# keyboardAV.net
KiCad netlist of a schematic drawn in EAGLE
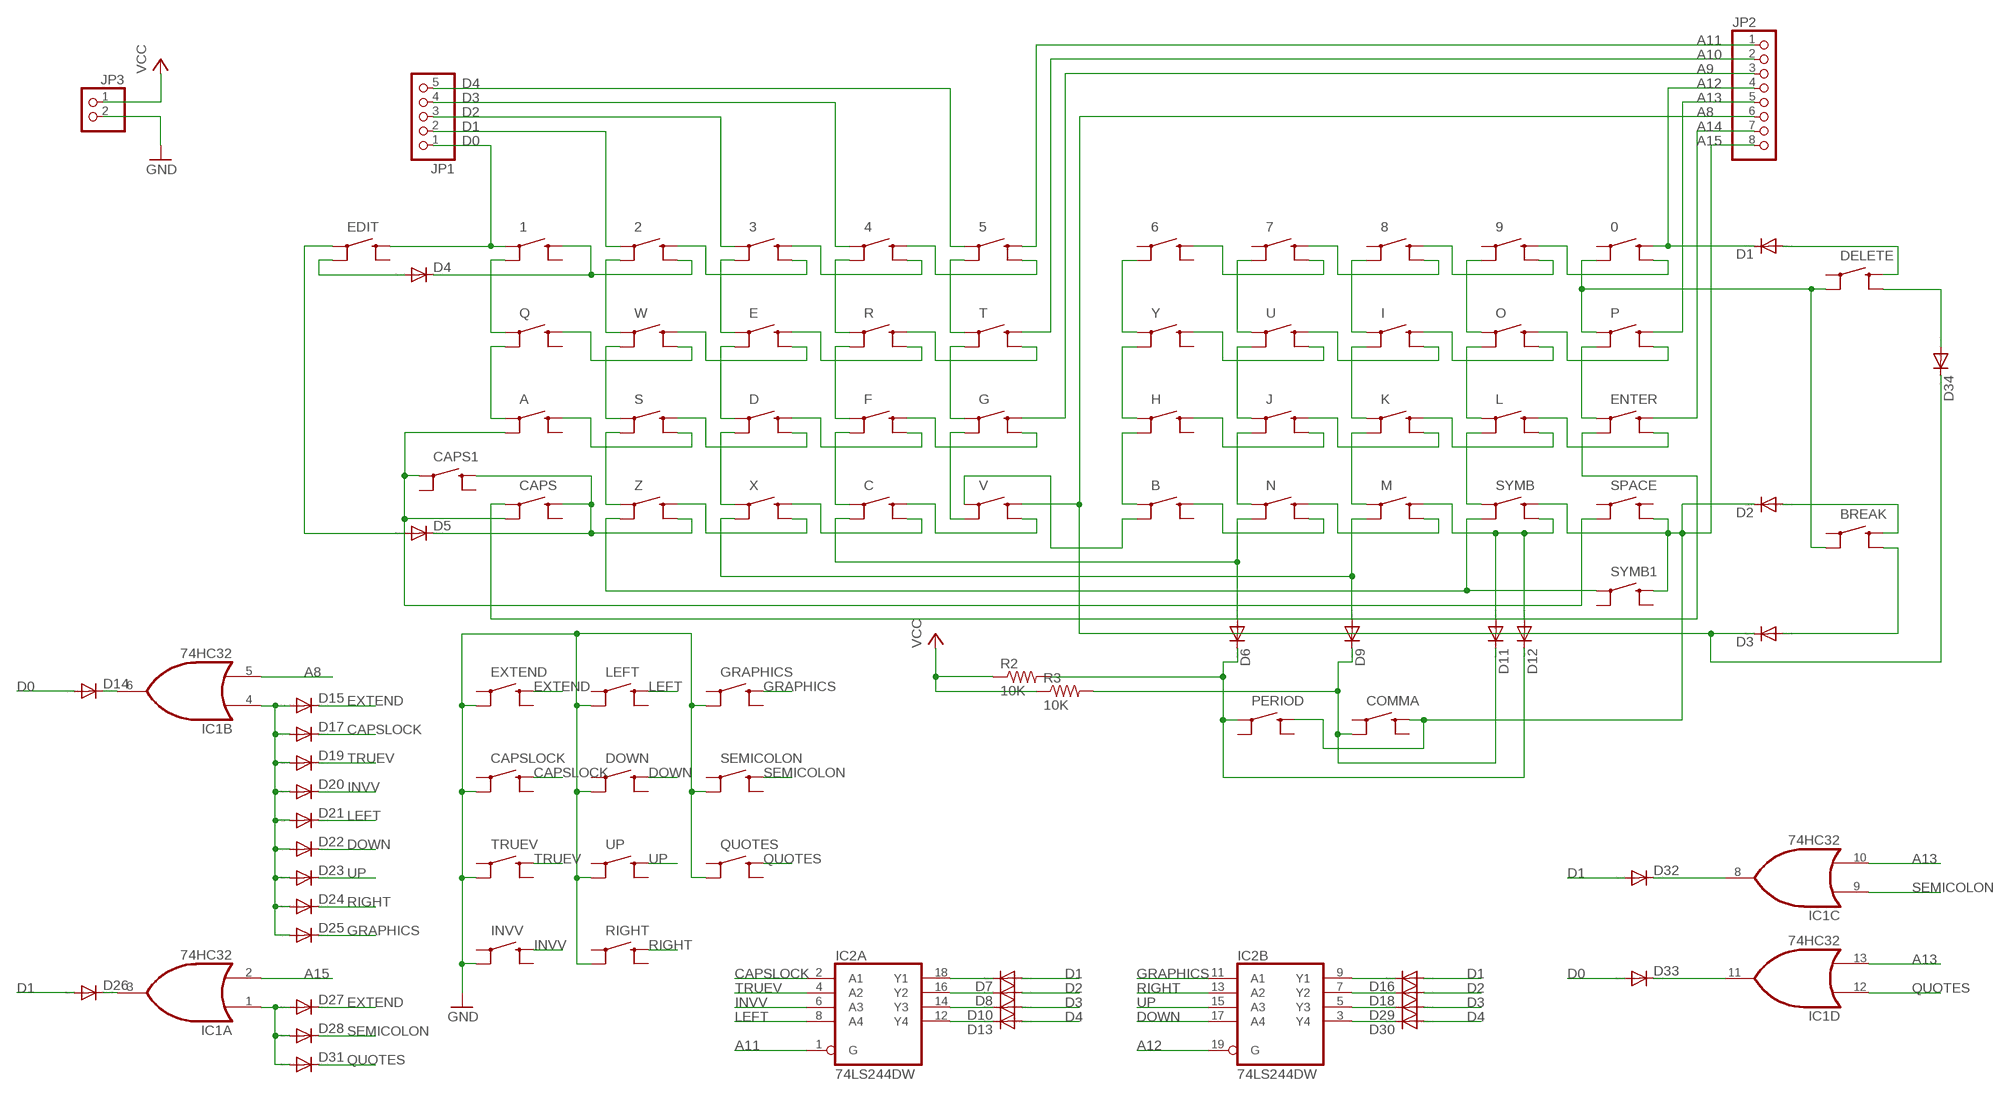
[diagram p0: schematic, sheet 1]

(export (version "E")
  (design (tool "Eeschema 10.0.6"))
  (components
    (comp (ref "0")
      (value "SWITCH-MOMENTARY-2SMD")
      (footprint "eagle-import:TACTILE-SWITCH-SMD")
      (libsource (lib "eagle-import") (part "SWITCH-MOMENTARY-2SMD"))
    )
    (comp (ref "1")
      (value "SWITCH-MOMENTARY-2SMD")
      (footprint "eagle-import:TACTILE-SWITCH-SMD")
      (libsource (lib "eagle-import") (part "SWITCH-MOMENTARY-2SMD"))
    )
    (comp (ref "2")
      (value "SWITCH-MOMENTARY-2SMD")
      (footprint "eagle-import:TACTILE-SWITCH-SMD")
      (libsource (lib "eagle-import") (part "SWITCH-MOMENTARY-2SMD"))
    )
    (comp (ref "3")
      (value "SWITCH-MOMENTARY-2SMD")
      (footprint "eagle-import:TACTILE-SWITCH-SMD")
      (libsource (lib "eagle-import") (part "SWITCH-MOMENTARY-2SMD"))
    )
    (comp (ref "4")
      (value "SWITCH-MOMENTARY-2SMD")
      (footprint "eagle-import:TACTILE-SWITCH-SMD")
      (libsource (lib "eagle-import") (part "SWITCH-MOMENTARY-2SMD"))
    )
    (comp (ref "5")
      (value "SWITCH-MOMENTARY-2SMD")
      (footprint "eagle-import:TACTILE-SWITCH-SMD")
      (libsource (lib "eagle-import") (part "SWITCH-MOMENTARY-2SMD"))
    )
    (comp (ref "6")
      (value "SWITCH-MOMENTARY-2SMD")
      (footprint "eagle-import:TACTILE-SWITCH-SMD")
      (libsource (lib "eagle-import") (part "SWITCH-MOMENTARY-2SMD"))
    )
    (comp (ref "7")
      (value "SWITCH-MOMENTARY-2SMD")
      (footprint "eagle-import:TACTILE-SWITCH-SMD")
      (libsource (lib "eagle-import") (part "SWITCH-MOMENTARY-2SMD"))
    )
    (comp (ref "8")
      (value "SWITCH-MOMENTARY-2SMD")
      (footprint "eagle-import:TACTILE-SWITCH-SMD")
      (libsource (lib "eagle-import") (part "SWITCH-MOMENTARY-2SMD"))
    )
    (comp (ref "9")
      (value "SWITCH-MOMENTARY-2SMD")
      (footprint "eagle-import:TACTILE-SWITCH-SMD")
      (libsource (lib "eagle-import") (part "SWITCH-MOMENTARY-2SMD"))
    )
    (comp (ref "A")
      (value "SWITCH-MOMENTARY-2SMD")
      (footprint "eagle-import:TACTILE-SWITCH-SMD")
      (libsource (lib "eagle-import") (part "SWITCH-MOMENTARY-2SMD"))
    )
    (comp (ref "B")
      (value "SWITCH-MOMENTARY-2SMD")
      (footprint "eagle-import:TACTILE-SWITCH-SMD")
      (libsource (lib "eagle-import") (part "SWITCH-MOMENTARY-2SMD"))
    )
    (comp (ref "BREAK")
      (value "SWITCH-MOMENTARY-2SMD")
      (footprint "eagle-import:TACTILE-SWITCH-SMD")
      (libsource (lib "eagle-import") (part "SWITCH-MOMENTARY-2SMD"))
    )
    (comp (ref "C")
      (value "SWITCH-MOMENTARY-2SMD")
      (footprint "eagle-import:TACTILE-SWITCH-SMD")
      (libsource (lib "eagle-import") (part "SWITCH-MOMENTARY-2SMD"))
    )
    (comp (ref "CAPS")
      (value "SWITCH-MOMENTARY-2SMD")
      (footprint "eagle-import:TACTILE-SWITCH-SMD")
      (libsource (lib "eagle-import") (part "SWITCH-MOMENTARY-2SMD"))
    )
    (comp (ref "CAPS1")
      (value "SWITCH-MOMENTARY-2SMD")
      (footprint "eagle-import:TACTILE-SWITCH-SMD")
      (libsource (lib "eagle-import") (part "SWITCH-MOMENTARY-2SMD"))
    )
    (comp (ref "CAPSLOCK")
      (value "SWITCH-MOMENTARY-2SMD")
      (footprint "eagle-import:TACTILE-SWITCH-SMD")
      (libsource (lib "eagle-import") (part "SWITCH-MOMENTARY-2SMD"))
    )
    (comp (ref "COMMA")
      (value "SWITCH-MOMENTARY-2SMD")
      (footprint "eagle-import:TACTILE-SWITCH-SMD")
      (libsource (lib "eagle-import") (part "SWITCH-MOMENTARY-2SMD"))
    )
    (comp (ref "D")
      (value "SWITCH-MOMENTARY-2SMD")
      (footprint "eagle-import:TACTILE-SWITCH-SMD")
      (libsource (lib "eagle-import") (part "SWITCH-MOMENTARY-2SMD"))
    )
    (comp (ref "D1")
      (value "DIODE-SOD323-R")
      (footprint "eagle-import:SOD323-R")
      (libsource (lib "eagle-import") (part "DIODE-SOD323-R"))
    )
    (comp (ref "D2")
      (value "DIODE-SOD323-R")
      (footprint "eagle-import:SOD323-R")
      (libsource (lib "eagle-import") (part "DIODE-SOD323-R"))
    )
    (comp (ref "D3")
      (value "DIODE-SOD323-R")
      (footprint "eagle-import:SOD323-R")
      (libsource (lib "eagle-import") (part "DIODE-SOD323-R"))
    )
    (comp (ref "D4")
      (value "DIODE-SOD323-R")
      (footprint "eagle-import:SOD323-R")
      (libsource (lib "eagle-import") (part "DIODE-SOD323-R"))
    )
    (comp (ref "D5")
      (value "DIODE-SOD323-R")
      (footprint "eagle-import:SOD323-R")
      (libsource (lib "eagle-import") (part "DIODE-SOD323-R"))
    )
    (comp (ref "D6")
      (value "DIODE-SOD323-R")
      (footprint "eagle-import:SOD323-R")
      (libsource (lib "eagle-import") (part "DIODE-SOD323-R"))
    )
    (comp (ref "D7")
      (value "DIODE-SOD323-R")
      (footprint "eagle-import:SOD323-R")
      (libsource (lib "eagle-import") (part "DIODE-SOD323-R"))
    )
    (comp (ref "D8")
      (value "DIODE-SOD323-R")
      (footprint "eagle-import:SOD323-R")
      (libsource (lib "eagle-import") (part "DIODE-SOD323-R"))
    )
    (comp (ref "D9")
      (value "DIODE-SOD323-R")
      (footprint "eagle-import:SOD323-R")
      (libsource (lib "eagle-import") (part "DIODE-SOD323-R"))
    )
    (comp (ref "D10")
      (value "DIODE-SOD323-R")
      (footprint "eagle-import:SOD323-R")
      (libsource (lib "eagle-import") (part "DIODE-SOD323-R"))
    )
    (comp (ref "D11")
      (value "DIODE-SOD323-R")
      (footprint "eagle-import:SOD323-R")
      (libsource (lib "eagle-import") (part "DIODE-SOD323-R"))
    )
    (comp (ref "D12")
      (value "DIODE-SOD323-R")
      (footprint "eagle-import:SOD323-R")
      (libsource (lib "eagle-import") (part "DIODE-SOD323-R"))
    )
    (comp (ref "D13")
      (value "DIODE-SOD323-R")
      (footprint "eagle-import:SOD323-R")
      (libsource (lib "eagle-import") (part "DIODE-SOD323-R"))
    )
    (comp (ref "D14")
      (value "DIODE-SOD323-R")
      (footprint "eagle-import:SOD323-R")
      (libsource (lib "eagle-import") (part "DIODE-SOD323-R"))
    )
    (comp (ref "D15")
      (value "DIODE-SOD323-R")
      (footprint "eagle-import:SOD323-R")
      (libsource (lib "eagle-import") (part "DIODE-SOD323-R"))
    )
    (comp (ref "D16")
      (value "DIODE-SOD323-R")
      (footprint "eagle-import:SOD323-R")
      (libsource (lib "eagle-import") (part "DIODE-SOD323-R"))
    )
    (comp (ref "D17")
      (value "DIODE-SOD323-R")
      (footprint "eagle-import:SOD323-R")
      (libsource (lib "eagle-import") (part "DIODE-SOD323-R"))
    )
    (comp (ref "D18")
      (value "DIODE-SOD323-R")
      (footprint "eagle-import:SOD323-R")
      (libsource (lib "eagle-import") (part "DIODE-SOD323-R"))
    )
    (comp (ref "D19")
      (value "DIODE-SOD323-R")
      (footprint "eagle-import:SOD323-R")
      (libsource (lib "eagle-import") (part "DIODE-SOD323-R"))
    )
    (comp (ref "D20")
      (value "DIODE-SOD323-R")
      (footprint "eagle-import:SOD323-R")
      (libsource (lib "eagle-import") (part "DIODE-SOD323-R"))
    )
    (comp (ref "D21")
      (value "DIODE-SOD323-R")
      (footprint "eagle-import:SOD323-R")
      (libsource (lib "eagle-import") (part "DIODE-SOD323-R"))
    )
    (comp (ref "D22")
      (value "DIODE-SOD323-R")
      (footprint "eagle-import:SOD323-R")
      (libsource (lib "eagle-import") (part "DIODE-SOD323-R"))
    )
    (comp (ref "D23")
      (value "DIODE-SOD323-R")
      (footprint "eagle-import:SOD323-R")
      (libsource (lib "eagle-import") (part "DIODE-SOD323-R"))
    )
    (comp (ref "D24")
      (value "DIODE-SOD323-R")
      (footprint "eagle-import:SOD323-R")
      (libsource (lib "eagle-import") (part "DIODE-SOD323-R"))
    )
    (comp (ref "D25")
      (value "DIODE-SOD323-R")
      (footprint "eagle-import:SOD323-R")
      (libsource (lib "eagle-import") (part "DIODE-SOD323-R"))
    )
    (comp (ref "D26")
      (value "DIODE-SOD323-R")
      (footprint "eagle-import:SOD323-R")
      (libsource (lib "eagle-import") (part "DIODE-SOD323-R"))
    )
    (comp (ref "D27")
      (value "DIODE-SOD323-R")
      (footprint "eagle-import:SOD323-R")
      (libsource (lib "eagle-import") (part "DIODE-SOD323-R"))
    )
    (comp (ref "D28")
      (value "DIODE-SOD323-R")
      (footprint "eagle-import:SOD323-R")
      (libsource (lib "eagle-import") (part "DIODE-SOD323-R"))
    )
    (comp (ref "D29")
      (value "DIODE-SOD323-R")
      (footprint "eagle-import:SOD323-R")
      (libsource (lib "eagle-import") (part "DIODE-SOD323-R"))
    )
    (comp (ref "D30")
      (value "DIODE-SOD323-R")
      (footprint "eagle-import:SOD323-R")
      (libsource (lib "eagle-import") (part "DIODE-SOD323-R"))
    )
    (comp (ref "D31")
      (value "DIODE-SOD323-R")
      (footprint "eagle-import:SOD323-R")
      (libsource (lib "eagle-import") (part "DIODE-SOD323-R"))
    )
    (comp (ref "D32")
      (value "DIODE-SOD323-R")
      (footprint "eagle-import:SOD323-R")
      (libsource (lib "eagle-import") (part "DIODE-SOD323-R"))
    )
    (comp (ref "D33")
      (value "DIODE-SOD323-R")
      (footprint "eagle-import:SOD323-R")
      (libsource (lib "eagle-import") (part "DIODE-SOD323-R"))
    )
    (comp (ref "D34")
      (value "DIODE-SOD323-R")
      (footprint "eagle-import:SOD323-R")
      (libsource (lib "eagle-import") (part "DIODE-SOD323-R"))
    )
    (comp (ref "DELETE")
      (value "SWITCH-MOMENTARY-2SMD")
      (footprint "eagle-import:TACTILE-SWITCH-SMD")
      (libsource (lib "eagle-import") (part "SWITCH-MOMENTARY-2SMD"))
    )
    (comp (ref "DOWN")
      (value "SWITCH-MOMENTARY-2SMD")
      (footprint "eagle-import:TACTILE-SWITCH-SMD")
      (libsource (lib "eagle-import") (part "SWITCH-MOMENTARY-2SMD"))
    )
    (comp (ref "E")
      (value "SWITCH-MOMENTARY-2SMD")
      (footprint "eagle-import:TACTILE-SWITCH-SMD")
      (libsource (lib "eagle-import") (part "SWITCH-MOMENTARY-2SMD"))
    )
    (comp (ref "EDIT")
      (value "SWITCH-MOMENTARY-2SMD")
      (footprint "eagle-import:TACTILE-SWITCH-SMD")
      (libsource (lib "eagle-import") (part "SWITCH-MOMENTARY-2SMD"))
    )
    (comp (ref "ENTER")
      (value "SWITCH-MOMENTARY-2SMD")
      (footprint "eagle-import:TACTILE-SWITCH-SMD")
      (libsource (lib "eagle-import") (part "SWITCH-MOMENTARY-2SMD"))
    )
    (comp (ref "EXTEND")
      (value "SWITCH-MOMENTARY-2SMD")
      (footprint "eagle-import:TACTILE-SWITCH-SMD")
      (libsource (lib "eagle-import") (part "SWITCH-MOMENTARY-2SMD"))
    )
    (comp (ref "F")
      (value "SWITCH-MOMENTARY-2SMD")
      (footprint "eagle-import:TACTILE-SWITCH-SMD")
      (libsource (lib "eagle-import") (part "SWITCH-MOMENTARY-2SMD"))
    )
    (comp (ref "G")
      (value "SWITCH-MOMENTARY-2SMD")
      (footprint "eagle-import:TACTILE-SWITCH-SMD")
      (libsource (lib "eagle-import") (part "SWITCH-MOMENTARY-2SMD"))
    )
    (comp (ref "GRAPHICS")
      (value "SWITCH-MOMENTARY-2SMD")
      (footprint "eagle-import:TACTILE-SWITCH-SMD")
      (libsource (lib "eagle-import") (part "SWITCH-MOMENTARY-2SMD"))
    )
    (comp (ref "H")
      (value "SWITCH-MOMENTARY-2SMD")
      (footprint "eagle-import:TACTILE-SWITCH-SMD")
      (libsource (lib "eagle-import") (part "SWITCH-MOMENTARY-2SMD"))
    )
    (comp (ref "I")
      (value "SWITCH-MOMENTARY-2SMD")
      (footprint "eagle-import:TACTILE-SWITCH-SMD")
      (libsource (lib "eagle-import") (part "SWITCH-MOMENTARY-2SMD"))
    )
    (comp (ref "IC1")
      (value "74HC32")
      (footprint "eagle-import:SO14")
      (libsource (lib "eagle-import") (part "7432DS"))
    )
    (comp (ref "IC2")
      (value "74LS244DW")
      (footprint "eagle-import:SO20W")
      (libsource (lib "eagle-import") (part "74244DWLS"))
    )
    (comp (ref "INVV")
      (value "SWITCH-MOMENTARY-2SMD")
      (footprint "eagle-import:TACTILE-SWITCH-SMD")
      (libsource (lib "eagle-import") (part "SWITCH-MOMENTARY-2SMD"))
    )
    (comp (ref "J")
      (value "SWITCH-MOMENTARY-2SMD")
      (footprint "eagle-import:TACTILE-SWITCH-SMD")
      (libsource (lib "eagle-import") (part "SWITCH-MOMENTARY-2SMD"))
    )
    (comp (ref "JP1")
      (value "PINHD-1X5")
      (footprint "eagle-import:1X05")
      (libsource (lib "eagle-import") (part "PINHD-1X5"))
    )
    (comp (ref "JP2")
      (value "PINHD-1X8")
      (footprint "eagle-import:1X08")
      (libsource (lib "eagle-import") (part "PINHD-1X8"))
    )
    (comp (ref "JP3")
      (value "PINHD-1X2")
      (footprint "eagle-import:1X02")
      (libsource (lib "eagle-import") (part "PINHD-1X2"))
    )
    (comp (ref "K")
      (value "SWITCH-MOMENTARY-2SMD")
      (footprint "eagle-import:TACTILE-SWITCH-SMD")
      (libsource (lib "eagle-import") (part "SWITCH-MOMENTARY-2SMD"))
    )
    (comp (ref "L")
      (value "SWITCH-MOMENTARY-2SMD")
      (footprint "eagle-import:TACTILE-SWITCH-SMD")
      (libsource (lib "eagle-import") (part "SWITCH-MOMENTARY-2SMD"))
    )
    (comp (ref "LEFT")
      (value "SWITCH-MOMENTARY-2SMD")
      (footprint "eagle-import:TACTILE-SWITCH-SMD")
      (libsource (lib "eagle-import") (part "SWITCH-MOMENTARY-2SMD"))
    )
    (comp (ref "M")
      (value "SWITCH-MOMENTARY-2SMD")
      (footprint "eagle-import:TACTILE-SWITCH-SMD")
      (libsource (lib "eagle-import") (part "SWITCH-MOMENTARY-2SMD"))
    )
    (comp (ref "N")
      (value "SWITCH-MOMENTARY-2SMD")
      (footprint "eagle-import:TACTILE-SWITCH-SMD")
      (libsource (lib "eagle-import") (part "SWITCH-MOMENTARY-2SMD"))
    )
    (comp (ref "O")
      (value "SWITCH-MOMENTARY-2SMD")
      (footprint "eagle-import:TACTILE-SWITCH-SMD")
      (libsource (lib "eagle-import") (part "SWITCH-MOMENTARY-2SMD"))
    )
    (comp (ref "P")
      (value "SWITCH-MOMENTARY-2SMD")
      (footprint "eagle-import:TACTILE-SWITCH-SMD")
      (libsource (lib "eagle-import") (part "SWITCH-MOMENTARY-2SMD"))
    )
    (comp (ref "PERIOD")
      (value "SWITCH-MOMENTARY-2SMD")
      (footprint "eagle-import:TACTILE-SWITCH-SMD")
      (libsource (lib "eagle-import") (part "SWITCH-MOMENTARY-2SMD"))
    )
    (comp (ref "Q")
      (value "SWITCH-MOMENTARY-2SMD")
      (footprint "eagle-import:TACTILE-SWITCH-SMD")
      (libsource (lib "eagle-import") (part "SWITCH-MOMENTARY-2SMD"))
    )
    (comp (ref "QUOTES")
      (value "SWITCH-MOMENTARY-2SMD")
      (footprint "eagle-import:TACTILE-SWITCH-SMD")
      (libsource (lib "eagle-import") (part "SWITCH-MOMENTARY-2SMD"))
    )
    (comp (ref "R")
      (value "SWITCH-MOMENTARY-2SMD")
      (footprint "eagle-import:TACTILE-SWITCH-SMD")
      (libsource (lib "eagle-import") (part "SWITCH-MOMENTARY-2SMD"))
    )
    (comp (ref "R2")
      (value "10K")
      (footprint "eagle-import:M0805")
      (libsource (lib "eagle-import") (part "R-US_M0805"))
    )
    (comp (ref "R3")
      (value "10K")
      (footprint "eagle-import:M0805")
      (libsource (lib "eagle-import") (part "R-US_M0805"))
    )
    (comp (ref "RIGHT")
      (value "SWITCH-MOMENTARY-2SMD")
      (footprint "eagle-import:TACTILE-SWITCH-SMD")
      (libsource (lib "eagle-import") (part "SWITCH-MOMENTARY-2SMD"))
    )
    (comp (ref "S")
      (value "SWITCH-MOMENTARY-2SMD")
      (footprint "eagle-import:TACTILE-SWITCH-SMD")
      (libsource (lib "eagle-import") (part "SWITCH-MOMENTARY-2SMD"))
    )
    (comp (ref "SEMICOLON")
      (value "SWITCH-MOMENTARY-2SMD")
      (footprint "eagle-import:TACTILE-SWITCH-SMD")
      (libsource (lib "eagle-import") (part "SWITCH-MOMENTARY-2SMD"))
    )
    (comp (ref "SPACE")
      (value "SWITCH-MOMENTARY-2SMD")
      (footprint "eagle-import:TACTILE-SWITCH-SMD")
      (libsource (lib "eagle-import") (part "SWITCH-MOMENTARY-2SMD"))
    )
    (comp (ref "SYMB")
      (value "SWITCH-MOMENTARY-2SMD")
      (footprint "eagle-import:TACTILE-SWITCH-SMD")
      (libsource (lib "eagle-import") (part "SWITCH-MOMENTARY-2SMD"))
    )
    (comp (ref "SYMB1")
      (value "SWITCH-MOMENTARY-2SMD")
      (footprint "eagle-import:TACTILE-SWITCH-SMD")
      (libsource (lib "eagle-import") (part "SWITCH-MOMENTARY-2SMD"))
    )
    (comp (ref "T")
      (value "SWITCH-MOMENTARY-2SMD")
      (footprint "eagle-import:TACTILE-SWITCH-SMD")
      (libsource (lib "eagle-import") (part "SWITCH-MOMENTARY-2SMD"))
    )
    (comp (ref "TRUEV")
      (value "SWITCH-MOMENTARY-2SMD")
      (footprint "eagle-import:TACTILE-SWITCH-SMD")
      (libsource (lib "eagle-import") (part "SWITCH-MOMENTARY-2SMD"))
    )
    (comp (ref "U")
      (value "SWITCH-MOMENTARY-2SMD")
      (footprint "eagle-import:TACTILE-SWITCH-SMD")
      (libsource (lib "eagle-import") (part "SWITCH-MOMENTARY-2SMD"))
    )
    (comp (ref "UP")
      (value "SWITCH-MOMENTARY-2SMD")
      (footprint "eagle-import:TACTILE-SWITCH-SMD")
      (libsource (lib "eagle-import") (part "SWITCH-MOMENTARY-2SMD"))
    )
    (comp (ref "V")
      (value "SWITCH-MOMENTARY-2SMD")
      (footprint "eagle-import:TACTILE-SWITCH-SMD")
      (libsource (lib "eagle-import") (part "SWITCH-MOMENTARY-2SMD"))
    )
    (comp (ref "W")
      (value "SWITCH-MOMENTARY-2SMD")
      (footprint "eagle-import:TACTILE-SWITCH-SMD")
      (libsource (lib "eagle-import") (part "SWITCH-MOMENTARY-2SMD"))
    )
    (comp (ref "X")
      (value "SWITCH-MOMENTARY-2SMD")
      (footprint "eagle-import:TACTILE-SWITCH-SMD")
      (libsource (lib "eagle-import") (part "SWITCH-MOMENTARY-2SMD"))
    )
    (comp (ref "Y")
      (value "SWITCH-MOMENTARY-2SMD")
      (footprint "eagle-import:TACTILE-SWITCH-SMD")
      (libsource (lib "eagle-import") (part "SWITCH-MOMENTARY-2SMD"))
    )
    (comp (ref "Z")
      (value "SWITCH-MOMENTARY-2SMD")
      (footprint "eagle-import:TACTILE-SWITCH-SMD")
      (libsource (lib "eagle-import") (part "SWITCH-MOMENTARY-2SMD"))
    )
  )
  (nets
    (net (code "1") (name "/A8") (class "Default")
      (node (ref "D3") (pin "C") (pinfunction "C_C") (pintype "passive"))
      (node (ref "D34") (pin "C") (pinfunction "C_C") (pintype "passive"))
      (node (ref "IC1") (pin "5") (pinfunction "I1_5") (pintype "input"))
      (node (ref "JP2") (pin "6") (pinfunction "6_6") (pintype "passive"))
      (node (ref "V") (pin "3") (pinfunction "2_3") (pintype "passive"))
    )
    (net (code "2") (name "/A9") (class "Default")
      (node (ref "G") (pin "3") (pinfunction "2_3") (pintype "passive"))
      (node (ref "JP2") (pin "3") (pinfunction "3_3") (pintype "passive"))
    )
    (net (code "3") (name "/A10") (class "Default")
      (node (ref "JP2") (pin "2") (pinfunction "2_2") (pintype "passive"))
      (node (ref "T") (pin "3") (pinfunction "2_3") (pintype "passive"))
    )
    (net (code "4") (name "/A11") (class "Default")
      (node (ref "5") (pin "3") (pinfunction "2_3") (pintype "passive"))
      (node (ref "IC2") (pin "1") (pinfunction "G_1") (pintype "input"))
      (node (ref "JP2") (pin "1") (pinfunction "1_1") (pintype "passive"))
    )
    (net (code "5") (name "/A12") (class "Default")
      (node (ref "0") (pin "3") (pinfunction "2_3") (pintype "passive"))
      (node (ref "D1") (pin "C") (pinfunction "C_C") (pintype "passive"))
      (node (ref "IC2") (pin "19") (pinfunction "G_19") (pintype "input"))
      (node (ref "JP2") (pin "4") (pinfunction "4_4") (pintype "passive"))
    )
    (net (code "6") (name "/A13") (class "Default")
      (node (ref "IC1") (pin "10") (pinfunction "I1_10") (pintype "input"))
      (node (ref "IC1") (pin "13") (pinfunction "I1_13") (pintype "input"))
      (node (ref "JP2") (pin "5") (pinfunction "5_5") (pintype "passive"))
      (node (ref "P") (pin "3") (pinfunction "2_3") (pintype "passive"))
    )
    (net (code "7") (name "/A14") (class "Default")
      (node (ref "ENTER") (pin "3") (pinfunction "2_3") (pintype "passive"))
      (node (ref "JP2") (pin "7") (pinfunction "7_7") (pintype "passive"))
    )
    (net (code "8") (name "/A15") (class "Default")
      (node (ref "COMMA") (pin "3") (pinfunction "2_3") (pintype "passive"))
      (node (ref "D2") (pin "C") (pinfunction "C_C") (pintype "passive"))
      (node (ref "IC1") (pin "2") (pinfunction "I1_2") (pintype "input"))
      (node (ref "JP2") (pin "8") (pinfunction "8_8") (pintype "passive"))
      (node (ref "PERIOD") (pin "3") (pinfunction "2_3") (pintype "passive"))
      (node (ref "SPACE") (pin "4") (pinfunction "4_4") (pintype "passive"))
      (node (ref "SYMB") (pin "3") (pinfunction "2_3") (pintype "passive"))
      (node (ref "SYMB1") (pin "3") (pinfunction "2_3") (pintype "passive"))
    )
    (net (code "9") (name "/CAPSLOCK") (class "Default")
      (node (ref "CAPSLOCK") (pin "3") (pinfunction "2_3") (pintype "passive"))
      (node (ref "D17") (pin "C") (pinfunction "C_C") (pintype "passive"))
      (node (ref "IC2") (pin "2") (pinfunction "A1_2") (pintype "input"))
    )
    (net (code "10") (name "/D0") (class "Default")
      (node (ref "1") (pin "1") (pinfunction "1_1") (pintype "passive"))
      (node (ref "D14") (pin "A") (pinfunction "A_A") (pintype "passive"))
      (node (ref "D33") (pin "A") (pinfunction "A_A") (pintype "passive"))
      (node (ref "EDIT") (pin "3") (pinfunction "2_3") (pintype "passive"))
      (node (ref "JP1") (pin "1") (pinfunction "1_1") (pintype "passive"))
    )
    (net (code "11") (name "/D1") (class "Default")
      (node (ref "2") (pin "1") (pinfunction "1_1") (pintype "passive"))
      (node (ref "D16") (pin "A") (pinfunction "A_A") (pintype "passive"))
      (node (ref "D26") (pin "A") (pinfunction "A_A") (pintype "passive"))
      (node (ref "D32") (pin "A") (pinfunction "A_A") (pintype "passive"))
      (node (ref "D7") (pin "A") (pinfunction "A_A") (pintype "passive"))
      (node (ref "JP1") (pin "2") (pinfunction "2_2") (pintype "passive"))
    )
    (net (code "12") (name "/D2") (class "Default")
      (node (ref "3") (pin "1") (pinfunction "1_1") (pintype "passive"))
      (node (ref "D18") (pin "A") (pinfunction "A_A") (pintype "passive"))
      (node (ref "D8") (pin "A") (pinfunction "A_A") (pintype "passive"))
      (node (ref "JP1") (pin "3") (pinfunction "3_3") (pintype "passive"))
    )
    (net (code "13") (name "/D3") (class "Default")
      (node (ref "4") (pin "1") (pinfunction "1_1") (pintype "passive"))
      (node (ref "D10") (pin "A") (pinfunction "A_A") (pintype "passive"))
      (node (ref "D29") (pin "A") (pinfunction "A_A") (pintype "passive"))
      (node (ref "JP1") (pin "4") (pinfunction "4_4") (pintype "passive"))
    )
    (net (code "14") (name "/D4") (class "Default")
      (node (ref "5") (pin "1") (pinfunction "1_1") (pintype "passive"))
      (node (ref "D13") (pin "A") (pinfunction "A_A") (pintype "passive"))
      (node (ref "D30") (pin "A") (pinfunction "A_A") (pintype "passive"))
      (node (ref "JP1") (pin "5") (pinfunction "5_5") (pintype "passive"))
    )
    (net (code "15") (name "/DOWN") (class "Default")
      (node (ref "D22") (pin "C") (pinfunction "C_C") (pintype "passive"))
      (node (ref "DOWN") (pin "3") (pinfunction "2_3") (pintype "passive"))
      (node (ref "IC2") (pin "17") (pinfunction "A4_17") (pintype "input"))
    )
    (net (code "16") (name "/EXTEND") (class "Default")
      (node (ref "D15") (pin "C") (pinfunction "C_C") (pintype "passive"))
      (node (ref "D27") (pin "C") (pinfunction "C_C") (pintype "passive"))
      (node (ref "EXTEND") (pin "3") (pinfunction "2_3") (pintype "passive"))
    )
    (net (code "17") (name "/GRAPHICS") (class "Default")
      (node (ref "D25") (pin "C") (pinfunction "C_C") (pintype "passive"))
      (node (ref "GRAPHICS") (pin "3") (pinfunction "2_3") (pintype "passive"))
      (node (ref "IC2") (pin "11") (pinfunction "A1_11") (pintype "input"))
    )
    (net (code "18") (name "/INVV") (class "Default")
      (node (ref "D20") (pin "C") (pinfunction "C_C") (pintype "passive"))
      (node (ref "IC2") (pin "6") (pinfunction "A3_6") (pintype "input"))
      (node (ref "INVV") (pin "3") (pinfunction "2_3") (pintype "passive"))
    )
    (net (code "19") (name "/LEFT") (class "Default")
      (node (ref "D21") (pin "C") (pinfunction "C_C") (pintype "passive"))
      (node (ref "IC2") (pin "8") (pinfunction "A4_8") (pintype "input"))
      (node (ref "LEFT") (pin "3") (pinfunction "2_3") (pintype "passive"))
    )
    (net (code "20") (name "/QUOTES") (class "Default")
      (node (ref "D31") (pin "C") (pinfunction "C_C") (pintype "passive"))
      (node (ref "IC1") (pin "12") (pinfunction "I0_12") (pintype "input"))
      (node (ref "QUOTES") (pin "3") (pinfunction "2_3") (pintype "passive"))
    )
    (net (code "21") (name "/RIGHT") (class "Default")
      (node (ref "D24") (pin "C") (pinfunction "C_C") (pintype "passive"))
      (node (ref "IC2") (pin "13") (pinfunction "A2_13") (pintype "input"))
      (node (ref "RIGHT") (pin "3") (pinfunction "2_3") (pintype "passive"))
    )
    (net (code "22") (name "/SEMICOLON") (class "Default")
      (node (ref "D28") (pin "C") (pinfunction "C_C") (pintype "passive"))
      (node (ref "IC1") (pin "9") (pinfunction "I0_9") (pintype "input"))
      (node (ref "SEMICOLON") (pin "3") (pinfunction "2_3") (pintype "passive"))
    )
    (net (code "23") (name "/TRUEV") (class "Default")
      (node (ref "D19") (pin "C") (pinfunction "C_C") (pintype "passive"))
      (node (ref "IC2") (pin "4") (pinfunction "A2_4") (pintype "input"))
      (node (ref "TRUEV") (pin "3") (pinfunction "2_3") (pintype "passive"))
    )
    (net (code "24") (name "/UP") (class "Default")
      (node (ref "D23") (pin "C") (pinfunction "C_C") (pintype "passive"))
      (node (ref "IC2") (pin "15") (pinfunction "A3_15") (pintype "input"))
      (node (ref "UP") (pin "3") (pinfunction "2_3") (pintype "passive"))
    )
    (net (code "25") (name "GND") (class "Default")
      (node (ref "CAPSLOCK") (pin "2") (pinfunction "3_2") (pintype "passive"))
      (node (ref "DOWN") (pin "2") (pinfunction "3_2") (pintype "passive"))
      (node (ref "EXTEND") (pin "2") (pinfunction "3_2") (pintype "passive"))
      (node (ref "GRAPHICS") (pin "2") (pinfunction "3_2") (pintype "passive"))
      (node (ref "INVV") (pin "2") (pinfunction "3_2") (pintype "passive"))
      (node (ref "JP3") (pin "2") (pinfunction "2_2") (pintype "passive"))
      (node (ref "LEFT") (pin "2") (pinfunction "3_2") (pintype "passive"))
      (node (ref "QUOTES") (pin "2") (pinfunction "3_2") (pintype "passive"))
      (node (ref "RIGHT") (pin "2") (pinfunction "3_2") (pintype "passive"))
      (node (ref "SEMICOLON") (pin "2") (pinfunction "3_2") (pintype "passive"))
      (node (ref "TRUEV") (pin "2") (pinfunction "3_2") (pintype "passive"))
      (node (ref "UP") (pin "2") (pinfunction "3_2") (pintype "passive"))
    )
    (net (code "26") (name "Net-(0-3)") (class "Default")
      (node (ref "0") (pin "2") (pinfunction "3_2") (pintype "passive"))
      (node (ref "BREAK") (pin "2") (pinfunction "3_2") (pintype "passive"))
      (node (ref "DELETE") (pin "2") (pinfunction "3_2") (pintype "passive"))
      (node (ref "P") (pin "1") (pinfunction "1_1") (pintype "passive"))
    )
    (net (code "27") (name "Net-(1-2)") (class "Default")
      (node (ref "1") (pin "3") (pinfunction "2_3") (pintype "passive"))
      (node (ref "2") (pin "4") (pinfunction "4_4") (pintype "passive"))
      (node (ref "D4") (pin "C") (pinfunction "C_C") (pintype "passive"))
    )
    (net (code "28") (name "Net-(1-3)") (class "Default")
      (node (ref "1") (pin "2") (pinfunction "3_2") (pintype "passive"))
      (node (ref "Q") (pin "1") (pinfunction "1_1") (pintype "passive"))
    )
    (net (code "29") (name "Net-(2-2)") (class "Default")
      (node (ref "2") (pin "3") (pinfunction "2_3") (pintype "passive"))
      (node (ref "3") (pin "4") (pinfunction "4_4") (pintype "passive"))
    )
    (net (code "30") (name "Net-(2-3)") (class "Default")
      (node (ref "2") (pin "2") (pinfunction "3_2") (pintype "passive"))
      (node (ref "W") (pin "1") (pinfunction "1_1") (pintype "passive"))
    )
    (net (code "31") (name "Net-(3-2)") (class "Default")
      (node (ref "3") (pin "3") (pinfunction "2_3") (pintype "passive"))
      (node (ref "4") (pin "4") (pinfunction "4_4") (pintype "passive"))
    )
    (net (code "32") (name "Net-(3-3)") (class "Default")
      (node (ref "3") (pin "2") (pinfunction "3_2") (pintype "passive"))
      (node (ref "E") (pin "1") (pinfunction "1_1") (pintype "passive"))
    )
    (net (code "33") (name "Net-(4-2)") (class "Default")
      (node (ref "4") (pin "3") (pinfunction "2_3") (pintype "passive"))
      (node (ref "5") (pin "4") (pinfunction "4_4") (pintype "passive"))
    )
    (net (code "34") (name "Net-(4-3)") (class "Default")
      (node (ref "4") (pin "2") (pinfunction "3_2") (pintype "passive"))
      (node (ref "R") (pin "1") (pinfunction "1_1") (pintype "passive"))
    )
    (net (code "35") (name "Net-(5-3)") (class "Default")
      (node (ref "5") (pin "2") (pinfunction "3_2") (pintype "passive"))
      (node (ref "T") (pin "1") (pinfunction "1_1") (pintype "passive"))
    )
    (net (code "36") (name "Net-(6-2)") (class "Default")
      (node (ref "6") (pin "3") (pinfunction "2_3") (pintype "passive"))
      (node (ref "7") (pin "4") (pinfunction "4_4") (pintype "passive"))
    )
    (net (code "37") (name "Net-(6-3)") (class "Default")
      (node (ref "6") (pin "2") (pinfunction "3_2") (pintype "passive"))
      (node (ref "Y") (pin "1") (pinfunction "1_1") (pintype "passive"))
    )
    (net (code "38") (name "Net-(7-2)") (class "Default")
      (node (ref "7") (pin "3") (pinfunction "2_3") (pintype "passive"))
      (node (ref "8") (pin "4") (pinfunction "4_4") (pintype "passive"))
    )
    (net (code "39") (name "Net-(7-3)") (class "Default")
      (node (ref "7") (pin "2") (pinfunction "3_2") (pintype "passive"))
      (node (ref "U") (pin "1") (pinfunction "1_1") (pintype "passive"))
    )
    (net (code "40") (name "Net-(8-2)") (class "Default")
      (node (ref "8") (pin "3") (pinfunction "2_3") (pintype "passive"))
      (node (ref "9") (pin "4") (pinfunction "4_4") (pintype "passive"))
    )
    (net (code "41") (name "Net-(8-3)") (class "Default")
      (node (ref "8") (pin "2") (pinfunction "3_2") (pintype "passive"))
      (node (ref "I") (pin "1") (pinfunction "1_1") (pintype "passive"))
    )
    (net (code "42") (name "Net-(9-2)") (class "Default")
      (node (ref "0") (pin "4") (pinfunction "4_4") (pintype "passive"))
      (node (ref "9") (pin "3") (pinfunction "2_3") (pintype "passive"))
    )
    (net (code "43") (name "Net-(9-3)") (class "Default")
      (node (ref "9") (pin "2") (pinfunction "3_2") (pintype "passive"))
      (node (ref "O") (pin "1") (pinfunction "1_1") (pintype "passive"))
    )
    (net (code "44") (name "Net-(A-2)") (class "Default")
      (node (ref "A") (pin "3") (pinfunction "2_3") (pintype "passive"))
      (node (ref "S") (pin "4") (pinfunction "4_4") (pintype "passive"))
    )
    (net (code "45") (name "Net-(A-3)") (class "Default")
      (node (ref "A") (pin "2") (pinfunction "3_2") (pintype "passive"))
      (node (ref "CAPS") (pin "2") (pinfunction "3_2") (pintype "passive"))
      (node (ref "CAPS1") (pin "1") (pinfunction "1_1") (pintype "passive"))
      (node (ref "SPACE") (pin "2") (pinfunction "3_2") (pintype "passive"))
    )
    (net (code "46") (name "Net-(B-2)") (class "Default")
      (node (ref "B") (pin "3") (pinfunction "2_3") (pintype "passive"))
      (node (ref "N") (pin "4") (pinfunction "4_4") (pintype "passive"))
    )
    (net (code "47") (name "Net-(B-3)") (class "Default")
      (node (ref "B") (pin "2") (pinfunction "3_2") (pintype "passive"))
      (node (ref "V") (pin "1") (pinfunction "1_1") (pintype "passive"))
    )
    (net (code "48") (name "Net-(BREAK-2)") (class "Default")
      (node (ref "BREAK") (pin "3") (pinfunction "2_3") (pintype "passive"))
      (node (ref "D2") (pin "A") (pinfunction "A_A") (pintype "passive"))
    )
    (net (code "49") (name "Net-(BREAK-Pad4)") (class "Default")
      (node (ref "BREAK") (pin "4") (pinfunction "4_4") (pintype "passive"))
      (node (ref "D3") (pin "A") (pinfunction "A_A") (pintype "passive"))
    )
    (net (code "50") (name "Net-(C-2)") (class "Default")
      (node (ref "C") (pin "3") (pinfunction "2_3") (pintype "passive"))
      (node (ref "V") (pin "4") (pinfunction "4_4") (pintype "passive"))
    )
    (net (code "51") (name "Net-(C-3)") (class "Default")
      (node (ref "C") (pin "2") (pinfunction "3_2") (pintype "passive"))
      (node (ref "D6") (pin "A") (pinfunction "A_A") (pintype "passive"))
      (node (ref "N") (pin "2") (pinfunction "3_2") (pintype "passive"))
    )
    (net (code "52") (name "Net-(CAPS-2)") (class "Default")
      (node (ref "CAPS") (pin "3") (pinfunction "2_3") (pintype "passive"))
      (node (ref "CAPS1") (pin "3") (pinfunction "2_3") (pintype "passive"))
      (node (ref "D5") (pin "C") (pinfunction "C_C") (pintype "passive"))
      (node (ref "Z") (pin "4") (pinfunction "4_4") (pintype "passive"))
    )
    (net (code "53") (name "Net-(COMMA-3)") (class "Default")
      (node (ref "COMMA") (pin "2") (pinfunction "3_2") (pintype "passive"))
      (node (ref "D11") (pin "C") (pinfunction "C_C") (pintype "passive"))
      (node (ref "D9") (pin "C") (pinfunction "C_C") (pintype "passive"))
      (node (ref "R3") (pin "2") (pinfunction "2_2") (pintype "passive"))
    )
    (net (code "54") (name "Net-(D-2)") (class "Default")
      (node (ref "D") (pin "3") (pinfunction "2_3") (pintype "passive"))
      (node (ref "F") (pin "4") (pinfunction "4_4") (pintype "passive"))
    )
    (net (code "55") (name "Net-(D-3)") (class "Default")
      (node (ref "D") (pin "2") (pinfunction "3_2") (pintype "passive"))
      (node (ref "X") (pin "1") (pinfunction "1_1") (pintype "passive"))
    )
    (net (code "56") (name "Net-(D5-PadA)") (class "Default")
      (node (ref "D5") (pin "A") (pinfunction "A_A") (pintype "passive"))
      (node (ref "EDIT") (pin "1") (pinfunction "1_1") (pintype "passive"))
    )
    (net (code "57") (name "Net-(D12-PadC)") (class "Default")
      (node (ref "D12") (pin "C") (pinfunction "C_C") (pintype "passive"))
      (node (ref "D6") (pin "C") (pinfunction "C_C") (pintype "passive"))
      (node (ref "PERIOD") (pin "1") (pinfunction "1_1") (pintype "passive"))
      (node (ref "R2") (pin "2") (pinfunction "2_2") (pintype "passive"))
    )
    (net (code "58") (name "Net-(D34-PadA)") (class "Default")
      (node (ref "D34") (pin "A") (pinfunction "A_A") (pintype "passive"))
      (node (ref "DELETE") (pin "4") (pinfunction "4_4") (pintype "passive"))
    )
    (net (code "59") (name "Net-(DELETE-2)") (class "Default")
      (node (ref "D1") (pin "A") (pinfunction "A_A") (pintype "passive"))
      (node (ref "DELETE") (pin "3") (pinfunction "2_3") (pintype "passive"))
    )
    (net (code "60") (name "Net-(E-2)") (class "Default")
      (node (ref "E") (pin "3") (pinfunction "2_3") (pintype "passive"))
      (node (ref "R") (pin "4") (pinfunction "4_4") (pintype "passive"))
    )
    (net (code "61") (name "Net-(E-3)") (class "Default")
      (node (ref "D") (pin "1") (pinfunction "1_1") (pintype "passive"))
      (node (ref "E") (pin "2") (pinfunction "3_2") (pintype "passive"))
    )
    (net (code "62") (name "Net-(EDIT-3)") (class "Default")
      (node (ref "D4") (pin "A") (pinfunction "A_A") (pintype "passive"))
      (node (ref "EDIT") (pin "2") (pinfunction "3_2") (pintype "passive"))
    )
    (net (code "63") (name "Net-(ENTER-3)") (class "Default")
      (node (ref "CAPS") (pin "1") (pinfunction "1_1") (pintype "passive"))
      (node (ref "ENTER") (pin "2") (pinfunction "3_2") (pintype "passive"))
    )
    (net (code "64") (name "Net-(F-2)") (class "Default")
      (node (ref "F") (pin "3") (pinfunction "2_3") (pintype "passive"))
      (node (ref "G") (pin "4") (pinfunction "4_4") (pintype "passive"))
    )
    (net (code "65") (name "Net-(F-3)") (class "Default")
      (node (ref "C") (pin "1") (pinfunction "1_1") (pintype "passive"))
      (node (ref "F") (pin "2") (pinfunction "3_2") (pintype "passive"))
    )
    (net (code "66") (name "Net-(G-3)") (class "Default")
      (node (ref "G") (pin "2") (pinfunction "3_2") (pintype "passive"))
      (node (ref "V") (pin "2") (pinfunction "3_2") (pintype "passive"))
    )
    (net (code "67") (name "Net-(H-2)") (class "Default")
      (node (ref "H") (pin "3") (pinfunction "2_3") (pintype "passive"))
      (node (ref "J") (pin "4") (pinfunction "4_4") (pintype "passive"))
    )
    (net (code "68") (name "Net-(H-3)") (class "Default")
      (node (ref "B") (pin "1") (pinfunction "1_1") (pintype "passive"))
      (node (ref "H") (pin "2") (pinfunction "3_2") (pintype "passive"))
    )
    (net (code "69") (name "Net-(I-2)") (class "Default")
      (node (ref "I") (pin "3") (pinfunction "2_3") (pintype "passive"))
      (node (ref "O") (pin "4") (pinfunction "4_4") (pintype "passive"))
    )
    (net (code "70") (name "Net-(I-3)") (class "Default")
      (node (ref "I") (pin "2") (pinfunction "3_2") (pintype "passive"))
      (node (ref "K") (pin "1") (pinfunction "1_1") (pintype "passive"))
    )
    (net (code "71") (name "Net-(IC1A-I0)") (class "Default")
      (node (ref "D27") (pin "A") (pinfunction "A_A") (pintype "passive"))
      (node (ref "D28") (pin "A") (pinfunction "A_A") (pintype "passive"))
      (node (ref "D31") (pin "A") (pinfunction "A_A") (pintype "passive"))
      (node (ref "IC1") (pin "1") (pinfunction "I0_1") (pintype "input"))
    )
    (net (code "72") (name "Net-(IC1A-O)") (class "Default")
      (node (ref "D26") (pin "C") (pinfunction "C_C") (pintype "passive"))
      (node (ref "IC1") (pin "3") (pinfunction "O_3") (pintype "output"))
    )
    (net (code "73") (name "Net-(IC1B-I0)") (class "Default")
      (node (ref "D15") (pin "A") (pinfunction "A_A") (pintype "passive"))
      (node (ref "D17") (pin "A") (pinfunction "A_A") (pintype "passive"))
      (node (ref "D19") (pin "A") (pinfunction "A_A") (pintype "passive"))
      (node (ref "D20") (pin "A") (pinfunction "A_A") (pintype "passive"))
      (node (ref "D21") (pin "A") (pinfunction "A_A") (pintype "passive"))
      (node (ref "D22") (pin "A") (pinfunction "A_A") (pintype "passive"))
      (node (ref "D23") (pin "A") (pinfunction "A_A") (pintype "passive"))
      (node (ref "D24") (pin "A") (pinfunction "A_A") (pintype "passive"))
      (node (ref "D25") (pin "A") (pinfunction "A_A") (pintype "passive"))
      (node (ref "IC1") (pin "4") (pinfunction "I0_4") (pintype "input"))
    )
    (net (code "74") (name "Net-(IC1B-O)") (class "Default")
      (node (ref "D14") (pin "C") (pinfunction "C_C") (pintype "passive"))
      (node (ref "IC1") (pin "6") (pinfunction "O_6") (pintype "output"))
    )
    (net (code "75") (name "Net-(IC1C-O)") (class "Default")
      (node (ref "D32") (pin "C") (pinfunction "C_C") (pintype "passive"))
      (node (ref "IC1") (pin "8") (pinfunction "O_8") (pintype "output"))
    )
    (net (code "76") (name "Net-(IC1D-O)") (class "Default")
      (node (ref "D33") (pin "C") (pinfunction "C_C") (pintype "passive"))
      (node (ref "IC1") (pin "11") (pinfunction "O_11") (pintype "output"))
    )
    (net (code "77") (name "Net-(IC2A-Y1)") (class "Default")
      (node (ref "D7") (pin "C") (pinfunction "C_C") (pintype "passive"))
      (node (ref "IC2") (pin "18") (pinfunction "Y1_18") (pintype "tri_state"))
    )
    (net (code "78") (name "Net-(IC2A-Y2)") (class "Default")
      (node (ref "D8") (pin "C") (pinfunction "C_C") (pintype "passive"))
      (node (ref "IC2") (pin "16") (pinfunction "Y2_16") (pintype "tri_state"))
    )
    (net (code "79") (name "Net-(IC2A-Y3)") (class "Default")
      (node (ref "D10") (pin "C") (pinfunction "C_C") (pintype "passive"))
      (node (ref "IC2") (pin "14") (pinfunction "Y3_14") (pintype "tri_state"))
    )
    (net (code "80") (name "Net-(IC2A-Y4)") (class "Default")
      (node (ref "D13") (pin "C") (pinfunction "C_C") (pintype "passive"))
      (node (ref "IC2") (pin "12") (pinfunction "Y4_12") (pintype "tri_state"))
    )
    (net (code "81") (name "Net-(IC2B-Y1)") (class "Default")
      (node (ref "D16") (pin "C") (pinfunction "C_C") (pintype "passive"))
      (node (ref "IC2") (pin "9") (pinfunction "Y1_9") (pintype "tri_state"))
    )
    (net (code "82") (name "Net-(IC2B-Y2)") (class "Default")
      (node (ref "D18") (pin "C") (pinfunction "C_C") (pintype "passive"))
      (node (ref "IC2") (pin "7") (pinfunction "Y2_7") (pintype "tri_state"))
    )
    (net (code "83") (name "Net-(IC2B-Y3)") (class "Default")
      (node (ref "D29") (pin "C") (pinfunction "C_C") (pintype "passive"))
      (node (ref "IC2") (pin "5") (pinfunction "Y3_5") (pintype "tri_state"))
    )
    (net (code "84") (name "Net-(IC2B-Y4)") (class "Default")
      (node (ref "D30") (pin "C") (pinfunction "C_C") (pintype "passive"))
      (node (ref "IC2") (pin "3") (pinfunction "Y4_3") (pintype "tri_state"))
    )
    (net (code "85") (name "Net-(J-2)") (class "Default")
      (node (ref "J") (pin "3") (pinfunction "2_3") (pintype "passive"))
      (node (ref "K") (pin "4") (pinfunction "4_4") (pintype "passive"))
    )
    (net (code "86") (name "Net-(J-3)") (class "Default")
      (node (ref "J") (pin "2") (pinfunction "3_2") (pintype "passive"))
      (node (ref "N") (pin "1") (pinfunction "1_1") (pintype "passive"))
    )
    (net (code "87") (name "Net-(K-2)") (class "Default")
      (node (ref "K") (pin "3") (pinfunction "2_3") (pintype "passive"))
      (node (ref "L") (pin "4") (pinfunction "4_4") (pintype "passive"))
    )
    (net (code "88") (name "Net-(K-3)") (class "Default")
      (node (ref "K") (pin "2") (pinfunction "3_2") (pintype "passive"))
      (node (ref "M") (pin "1") (pinfunction "1_1") (pintype "passive"))
    )
    (net (code "89") (name "Net-(L-2)") (class "Default")
      (node (ref "ENTER") (pin "4") (pinfunction "4_4") (pintype "passive"))
      (node (ref "L") (pin "3") (pinfunction "2_3") (pintype "passive"))
    )
    (net (code "90") (name "Net-(L-3)") (class "Default")
      (node (ref "L") (pin "2") (pinfunction "3_2") (pintype "passive"))
      (node (ref "SYMB") (pin "1") (pinfunction "1_1") (pintype "passive"))
    )
    (net (code "91") (name "Net-(M-2)") (class "Default")
      (node (ref "D11") (pin "A") (pinfunction "A_A") (pintype "passive"))
      (node (ref "D12") (pin "A") (pinfunction "A_A") (pintype "passive"))
      (node (ref "M") (pin "3") (pinfunction "2_3") (pintype "passive"))
      (node (ref "SYMB") (pin "4") (pinfunction "4_4") (pintype "passive"))
    )
    (net (code "92") (name "Net-(M-3)") (class "Default")
      (node (ref "D9") (pin "A") (pinfunction "A_A") (pintype "passive"))
      (node (ref "M") (pin "2") (pinfunction "3_2") (pintype "passive"))
      (node (ref "X") (pin "2") (pinfunction "3_2") (pintype "passive"))
    )
    (net (code "93") (name "Net-(N-2)") (class "Default")
      (node (ref "M") (pin "4") (pinfunction "4_4") (pintype "passive"))
      (node (ref "N") (pin "3") (pinfunction "2_3") (pintype "passive"))
    )
    (net (code "94") (name "Net-(O-2)") (class "Default")
      (node (ref "O") (pin "3") (pinfunction "2_3") (pintype "passive"))
      (node (ref "P") (pin "4") (pinfunction "4_4") (pintype "passive"))
    )
    (net (code "95") (name "Net-(O-3)") (class "Default")
      (node (ref "L") (pin "1") (pinfunction "1_1") (pintype "passive"))
      (node (ref "O") (pin "2") (pinfunction "3_2") (pintype "passive"))
    )
    (net (code "96") (name "Net-(P-3)") (class "Default")
      (node (ref "ENTER") (pin "1") (pinfunction "1_1") (pintype "passive"))
      (node (ref "P") (pin "2") (pinfunction "3_2") (pintype "passive"))
    )
    (net (code "97") (name "Net-(Q-2)") (class "Default")
      (node (ref "Q") (pin "3") (pinfunction "2_3") (pintype "passive"))
      (node (ref "W") (pin "4") (pinfunction "4_4") (pintype "passive"))
    )
    (net (code "98") (name "Net-(Q-3)") (class "Default")
      (node (ref "A") (pin "1") (pinfunction "1_1") (pintype "passive"))
      (node (ref "Q") (pin "2") (pinfunction "3_2") (pintype "passive"))
    )
    (net (code "99") (name "Net-(R-2)") (class "Default")
      (node (ref "R") (pin "3") (pinfunction "2_3") (pintype "passive"))
      (node (ref "T") (pin "4") (pinfunction "4_4") (pintype "passive"))
    )
    (net (code "100") (name "Net-(R-3)") (class "Default")
      (node (ref "F") (pin "1") (pinfunction "1_1") (pintype "passive"))
      (node (ref "R") (pin "2") (pinfunction "3_2") (pintype "passive"))
    )
    (net (code "101") (name "Net-(S-2)") (class "Default")
      (node (ref "D") (pin "4") (pinfunction "4_4") (pintype "passive"))
      (node (ref "S") (pin "3") (pinfunction "2_3") (pintype "passive"))
    )
    (net (code "102") (name "Net-(S-3)") (class "Default")
      (node (ref "S") (pin "2") (pinfunction "3_2") (pintype "passive"))
      (node (ref "Z") (pin "1") (pinfunction "1_1") (pintype "passive"))
    )
    (net (code "103") (name "Net-(SYMB-3)") (class "Default")
      (node (ref "SYMB") (pin "2") (pinfunction "3_2") (pintype "passive"))
      (node (ref "SYMB1") (pin "1") (pinfunction "1_1") (pintype "passive"))
      (node (ref "Z") (pin "2") (pinfunction "3_2") (pintype "passive"))
    )
    (net (code "104") (name "Net-(T-3)") (class "Default")
      (node (ref "G") (pin "1") (pinfunction "1_1") (pintype "passive"))
      (node (ref "T") (pin "2") (pinfunction "3_2") (pintype "passive"))
    )
    (net (code "105") (name "Net-(U-2)") (class "Default")
      (node (ref "I") (pin "4") (pinfunction "4_4") (pintype "passive"))
      (node (ref "U") (pin "3") (pinfunction "2_3") (pintype "passive"))
    )
    (net (code "106") (name "Net-(U-3)") (class "Default")
      (node (ref "J") (pin "1") (pinfunction "1_1") (pintype "passive"))
      (node (ref "U") (pin "2") (pinfunction "3_2") (pintype "passive"))
    )
    (net (code "107") (name "Net-(W-2)") (class "Default")
      (node (ref "E") (pin "4") (pinfunction "4_4") (pintype "passive"))
      (node (ref "W") (pin "3") (pinfunction "2_3") (pintype "passive"))
    )
    (net (code "108") (name "Net-(W-3)") (class "Default")
      (node (ref "S") (pin "1") (pinfunction "1_1") (pintype "passive"))
      (node (ref "W") (pin "2") (pinfunction "3_2") (pintype "passive"))
    )
    (net (code "109") (name "Net-(X-2)") (class "Default")
      (node (ref "C") (pin "4") (pinfunction "4_4") (pintype "passive"))
      (node (ref "X") (pin "3") (pinfunction "2_3") (pintype "passive"))
    )
    (net (code "110") (name "Net-(Y-2)") (class "Default")
      (node (ref "U") (pin "4") (pinfunction "4_4") (pintype "passive"))
      (node (ref "Y") (pin "3") (pinfunction "2_3") (pintype "passive"))
    )
    (net (code "111") (name "Net-(Y-3)") (class "Default")
      (node (ref "H") (pin "1") (pinfunction "1_1") (pintype "passive"))
      (node (ref "Y") (pin "2") (pinfunction "3_2") (pintype "passive"))
    )
    (net (code "112") (name "Net-(Z-2)") (class "Default")
      (node (ref "X") (pin "4") (pinfunction "4_4") (pintype "passive"))
      (node (ref "Z") (pin "3") (pinfunction "2_3") (pintype "passive"))
    )
    (net (code "113") (name "VCC") (class "Default")
      (node (ref "JP3") (pin "1") (pinfunction "1_1") (pintype "passive"))
      (node (ref "R2") (pin "1") (pinfunction "1_1") (pintype "passive"))
      (node (ref "R3") (pin "1") (pinfunction "1_1") (pintype "passive"))
    )
    (net (code "114") (name "unconnected-(0-Pad1)") (class "Default")
      (node (ref "0") (pin "1") (pinfunction "1_1") (pintype "passive"))
    )
    (net (code "115") (name "unconnected-(1-Pad4)") (class "Default")
      (node (ref "1") (pin "4") (pinfunction "4_4") (pintype "passive"))
    )
    (net (code "116") (name "unconnected-(6-Pad1)") (class "Default")
      (node (ref "6") (pin "1") (pinfunction "1_1") (pintype "passive"))
    )
    (net (code "117") (name "unconnected-(6-Pad4)") (class "Default")
      (node (ref "6") (pin "4") (pinfunction "4_4") (pintype "passive"))
    )
    (net (code "118") (name "unconnected-(7-Pad1)") (class "Default")
      (node (ref "7") (pin "1") (pinfunction "1_1") (pintype "passive"))
    )
    (net (code "119") (name "unconnected-(8-Pad1)") (class "Default")
      (node (ref "8") (pin "1") (pinfunction "1_1") (pintype "passive"))
    )
    (net (code "120") (name "unconnected-(9-Pad1)") (class "Default")
      (node (ref "9") (pin "1") (pinfunction "1_1") (pintype "passive"))
    )
    (net (code "121") (name "unconnected-(A-Pad4)") (class "Default")
      (node (ref "A") (pin "4") (pinfunction "4_4") (pintype "passive"))
    )
    (net (code "122") (name "unconnected-(B-Pad4)") (class "Default")
      (node (ref "B") (pin "4") (pinfunction "4_4") (pintype "passive"))
    )
    (net (code "123") (name "unconnected-(BREAK-Pad1)") (class "Default")
      (node (ref "BREAK") (pin "1") (pinfunction "1_1") (pintype "passive"))
    )
    (net (code "124") (name "unconnected-(CAPS-Pad4)") (class "Default")
      (node (ref "CAPS") (pin "4") (pinfunction "4_4") (pintype "passive"))
    )
    (net (code "125") (name "unconnected-(CAPS1-3-Pad2)") (class "Default")
      (node (ref "CAPS1") (pin "2") (pinfunction "3_2") (pintype "passive"))
    )
    (net (code "126") (name "unconnected-(CAPS1-Pad4)") (class "Default")
      (node (ref "CAPS1") (pin "4") (pinfunction "4_4") (pintype "passive"))
    )
    (net (code "127") (name "unconnected-(CAPSLOCK-Pad1)") (class "Default")
      (node (ref "CAPSLOCK") (pin "1") (pinfunction "1_1") (pintype "passive"))
    )
    (net (code "128") (name "unconnected-(CAPSLOCK-Pad4)") (class "Default")
      (node (ref "CAPSLOCK") (pin "4") (pinfunction "4_4") (pintype "passive"))
    )
    (net (code "129") (name "unconnected-(COMMA-Pad1)") (class "Default")
      (node (ref "COMMA") (pin "1") (pinfunction "1_1") (pintype "passive"))
    )
    (net (code "130") (name "unconnected-(COMMA-Pad4)") (class "Default")
      (node (ref "COMMA") (pin "4") (pinfunction "4_4") (pintype "passive"))
    )
    (net (code "131") (name "unconnected-(DELETE-Pad1)") (class "Default")
      (node (ref "DELETE") (pin "1") (pinfunction "1_1") (pintype "passive"))
    )
    (net (code "132") (name "unconnected-(DOWN-Pad1)") (class "Default")
      (node (ref "DOWN") (pin "1") (pinfunction "1_1") (pintype "passive"))
    )
    (net (code "133") (name "unconnected-(DOWN-Pad4)") (class "Default")
      (node (ref "DOWN") (pin "4") (pinfunction "4_4") (pintype "passive"))
    )
    (net (code "134") (name "unconnected-(EDIT-Pad4)") (class "Default")
      (node (ref "EDIT") (pin "4") (pinfunction "4_4") (pintype "passive"))
    )
    (net (code "135") (name "unconnected-(EXTEND-Pad1)") (class "Default")
      (node (ref "EXTEND") (pin "1") (pinfunction "1_1") (pintype "passive"))
    )
    (net (code "136") (name "unconnected-(EXTEND-Pad4)") (class "Default")
      (node (ref "EXTEND") (pin "4") (pinfunction "4_4") (pintype "passive"))
    )
    (net (code "137") (name "unconnected-(GRAPHICS-Pad1)") (class "Default")
      (node (ref "GRAPHICS") (pin "1") (pinfunction "1_1") (pintype "passive"))
    )
    (net (code "138") (name "unconnected-(GRAPHICS-Pad4)") (class "Default")
      (node (ref "GRAPHICS") (pin "4") (pinfunction "4_4") (pintype "passive"))
    )
    (net (code "139") (name "unconnected-(H-Pad4)") (class "Default")
      (node (ref "H") (pin "4") (pinfunction "4_4") (pintype "passive"))
    )
    (net (code "140") (name "unconnected-(INVV-Pad1)") (class "Default")
      (node (ref "INVV") (pin "1") (pinfunction "1_1") (pintype "passive"))
    )
    (net (code "141") (name "unconnected-(INVV-Pad4)") (class "Default")
      (node (ref "INVV") (pin "4") (pinfunction "4_4") (pintype "passive"))
    )
    (net (code "142") (name "unconnected-(LEFT-Pad1)") (class "Default")
      (node (ref "LEFT") (pin "1") (pinfunction "1_1") (pintype "passive"))
    )
    (net (code "143") (name "unconnected-(LEFT-Pad4)") (class "Default")
      (node (ref "LEFT") (pin "4") (pinfunction "4_4") (pintype "passive"))
    )
    (net (code "144") (name "unconnected-(PERIOD-3-Pad2)") (class "Default")
      (node (ref "PERIOD") (pin "2") (pinfunction "3_2") (pintype "passive"))
    )
    (net (code "145") (name "unconnected-(PERIOD-Pad4)") (class "Default")
      (node (ref "PERIOD") (pin "4") (pinfunction "4_4") (pintype "passive"))
    )
    (net (code "146") (name "unconnected-(Q-Pad4)") (class "Default")
      (node (ref "Q") (pin "4") (pinfunction "4_4") (pintype "passive"))
    )
    (net (code "147") (name "unconnected-(QUOTES-Pad1)") (class "Default")
      (node (ref "QUOTES") (pin "1") (pinfunction "1_1") (pintype "passive"))
    )
    (net (code "148") (name "unconnected-(QUOTES-Pad4)") (class "Default")
      (node (ref "QUOTES") (pin "4") (pinfunction "4_4") (pintype "passive"))
    )
    (net (code "149") (name "unconnected-(RIGHT-Pad1)") (class "Default")
      (node (ref "RIGHT") (pin "1") (pinfunction "1_1") (pintype "passive"))
    )
    (net (code "150") (name "unconnected-(RIGHT-Pad4)") (class "Default")
      (node (ref "RIGHT") (pin "4") (pinfunction "4_4") (pintype "passive"))
    )
    (net (code "151") (name "unconnected-(SEMICOLON-Pad1)") (class "Default")
      (node (ref "SEMICOLON") (pin "1") (pinfunction "1_1") (pintype "passive"))
    )
    (net (code "152") (name "unconnected-(SEMICOLON-Pad4)") (class "Default")
      (node (ref "SEMICOLON") (pin "4") (pinfunction "4_4") (pintype "passive"))
    )
    (net (code "153") (name "unconnected-(SPACE-2-Pad3)") (class "Default")
      (node (ref "SPACE") (pin "3") (pinfunction "2_3") (pintype "passive"))
    )
    (net (code "154") (name "unconnected-(SPACE-Pad1)") (class "Default")
      (node (ref "SPACE") (pin "1") (pinfunction "1_1") (pintype "passive"))
    )
    (net (code "155") (name "unconnected-(SYMB1-3-Pad2)") (class "Default")
      (node (ref "SYMB1") (pin "2") (pinfunction "3_2") (pintype "passive"))
    )
    (net (code "156") (name "unconnected-(SYMB1-Pad4)") (class "Default")
      (node (ref "SYMB1") (pin "4") (pinfunction "4_4") (pintype "passive"))
    )
    (net (code "157") (name "unconnected-(TRUEV-Pad1)") (class "Default")
      (node (ref "TRUEV") (pin "1") (pinfunction "1_1") (pintype "passive"))
    )
    (net (code "158") (name "unconnected-(TRUEV-Pad4)") (class "Default")
      (node (ref "TRUEV") (pin "4") (pinfunction "4_4") (pintype "passive"))
    )
    (net (code "159") (name "unconnected-(UP-Pad1)") (class "Default")
      (node (ref "UP") (pin "1") (pinfunction "1_1") (pintype "passive"))
    )
    (net (code "160") (name "unconnected-(UP-Pad4)") (class "Default")
      (node (ref "UP") (pin "4") (pinfunction "4_4") (pintype "passive"))
    )
    (net (code "161") (name "unconnected-(Y-Pad4)") (class "Default")
      (node (ref "Y") (pin "4") (pinfunction "4_4") (pintype "passive"))
    )
  )
)
